# LED_Bar.net
KiCad netlist of a schematic drawn in Altium Designer
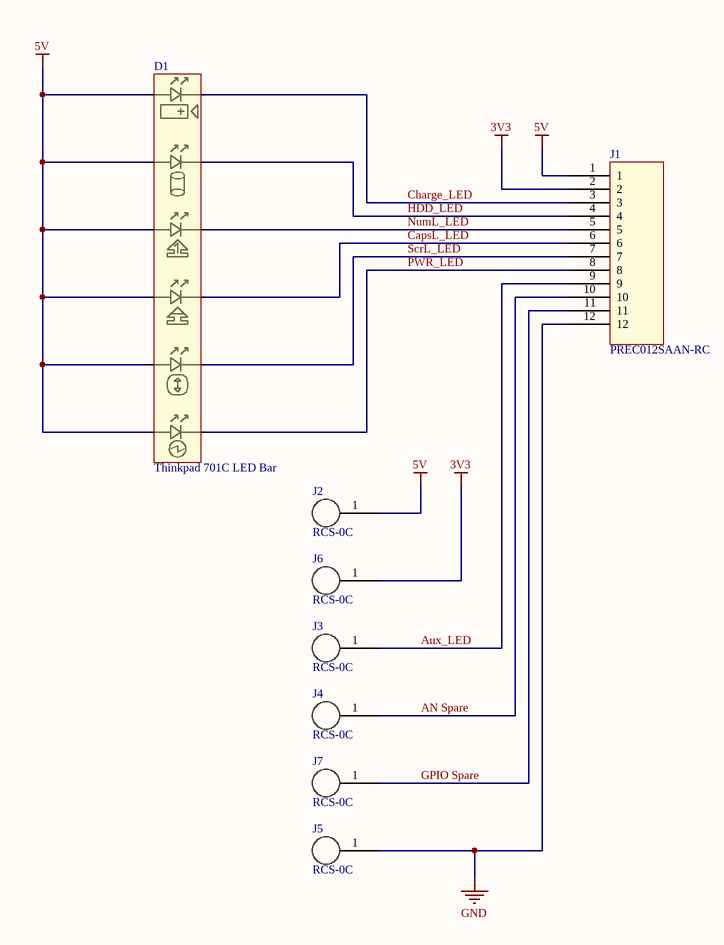
[diagram p0: LED Bar.SchDoc]

(export (version "E")
  (design (tool "Eeschema 10.0.6"))
  (components
    (comp (ref "D1")
      (value "Thinkpad 701C LED Bar")
      (footprint "TP701C LED Bar")
      (libsource (lib "KBuchka-IntLib") (part "Thinkpad 701C LED Bar"))
    )
    (comp (ref "J1")
      (value "PREC012SAAN-RC")
      (footprint "PREC012SAAN-RC")
      (description "CONN HDR 12POS 0.1 TIN PCB")
      (libsource (lib "KBuchka-IntLib") (part "PREC012SAAN-RC"))
    )
    (comp (ref "J2") (value "RCS-0C") (footprint "RCS-0C") (libsource (lib "KBuchka-IntLib") (part "RCS-0C")))
    (comp (ref "J3") (value "RCS-0C") (footprint "RCS-0C") (libsource (lib "KBuchka-IntLib") (part "RCS-0C")))
    (comp (ref "J4") (value "RCS-0C") (footprint "RCS-0C") (libsource (lib "KBuchka-IntLib") (part "RCS-0C")))
    (comp (ref "J5") (value "RCS-0C") (footprint "RCS-0C") (libsource (lib "KBuchka-IntLib") (part "RCS-0C")))
    (comp (ref "J6") (value "RCS-0C") (footprint "RCS-0C") (libsource (lib "KBuchka-IntLib") (part "RCS-0C")))
    (comp (ref "J7") (value "RCS-0C") (footprint "RCS-0C") (libsource (lib "KBuchka-IntLib") (part "RCS-0C")))
  )
  (nets
    (net (code "1") (name "/AN Spare") (class "Default")
      (node (ref "J1") (pin "10") (pinfunction "10_10") (pintype "passive"))
      (node (ref "J4") (pin "1") (pinfunction "1_1") (pintype "passive"))
    )
    (net (code "2") (name "/Aux_LED") (class "Default")
      (node (ref "J1") (pin "9") (pinfunction "9_9") (pintype "passive"))
      (node (ref "J3") (pin "1") (pinfunction "1_1") (pintype "passive"))
    )
    (net (code "3") (name "/CapsL_LED") (class "Default")
      (node (ref "D1") (pin "8") (pinfunction "1_8") (pintype "passive"))
      (node (ref "J1") (pin "6") (pinfunction "6_6") (pintype "passive"))
    )
    (net (code "4") (name "/Charge_LED") (class "Default")
      (node (ref "D1") (pin "2") (pinfunction "1_2") (pintype "passive"))
      (node (ref "J1") (pin "3") (pinfunction "3_3") (pintype "passive"))
    )
    (net (code "5") (name "/GPIO Spare") (class "Default")
      (node (ref "J1") (pin "11") (pinfunction "11_11") (pintype "passive"))
      (node (ref "J7") (pin "1") (pinfunction "1_1") (pintype "passive"))
    )
    (net (code "6") (name "/HDD_LED") (class "Default")
      (node (ref "D1") (pin "4") (pinfunction "1_4") (pintype "passive"))
      (node (ref "J1") (pin "4") (pinfunction "4_4") (pintype "passive"))
    )
    (net (code "7") (name "/NumL_LED") (class "Default")
      (node (ref "D1") (pin "6") (pinfunction "1_6") (pintype "passive"))
      (node (ref "J1") (pin "5") (pinfunction "5_5") (pintype "passive"))
    )
    (net (code "8") (name "/PWR_LED") (class "Default")
      (node (ref "D1") (pin "12") (pinfunction "1_12") (pintype "passive"))
      (node (ref "J1") (pin "8") (pinfunction "8_8") (pintype "passive"))
    )
    (net (code "9") (name "/ScrL_LED") (class "Default")
      (node (ref "D1") (pin "10") (pinfunction "1_10") (pintype "passive"))
      (node (ref "J1") (pin "7") (pinfunction "7_7") (pintype "passive"))
    )
    (net (code "10") (name "3V3") (class "Default")
      (node (ref "J1") (pin "2") (pinfunction "2_2") (pintype "passive"))
      (node (ref "J6") (pin "1") (pinfunction "1_1") (pintype "passive"))
    )
    (net (code "11") (name "5V") (class "Default")
      (node (ref "D1") (pin "1") (pinfunction "2_1") (pintype "passive"))
      (node (ref "D1") (pin "11") (pinfunction "2_11") (pintype "passive"))
      (node (ref "D1") (pin "3") (pinfunction "2_3") (pintype "passive"))
      (node (ref "D1") (pin "5") (pinfunction "2_5") (pintype "passive"))
      (node (ref "D1") (pin "7") (pinfunction "2_7") (pintype "passive"))
      (node (ref "D1") (pin "9") (pinfunction "2_9") (pintype "passive"))
      (node (ref "J1") (pin "1") (pinfunction "1_1") (pintype "passive"))
      (node (ref "J2") (pin "1") (pinfunction "1_1") (pintype "passive"))
    )
    (net (code "12") (name "GND") (class "Default")
      (node (ref "J1") (pin "12") (pinfunction "12_12") (pintype "passive"))
      (node (ref "J5") (pin "1") (pinfunction "1_1") (pintype "passive"))
    )
  )
)
